# TailBoard.net
KiCad netlist of a schematic drawn in Altium Designer
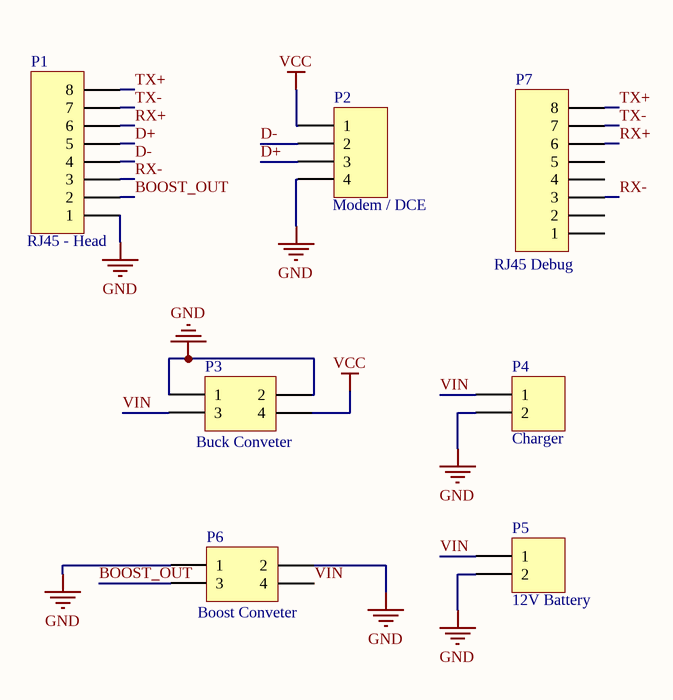
[diagram p0: TailBoard.SchDoc]

(export (version "E")
  (design (tool "Eeschema 10.0.6"))
  (components
    (comp (ref "P1")
      (value "RJ45 - Head")
      (footprint "RJ45")
      (description "Header, 8-Pin")
      (fields (field (name "PUBLISHER") "Altium Limited"))
      (libsource (lib "Miscellaneous Connectors") (part "Header 8"))
    )
    (comp (ref "P2")
      (value "Modem / DCE")
      (footprint "USB_Female")
      (description "Header, 4-Pin")
      (fields (field (name "PUBLISHER") "Altium Limited"))
      (libsource (lib "Miscellaneous Connectors") (part "Header 4"))
    )
    (comp (ref "P3")
      (value "Buck Conveter")
      (footprint "PWR_HEADER")
      (description "Header, 2-Pin, Dual row")
      (fields (field (name "PUBLISHER") "Altium Limited"))
      (libsource (lib "Miscellaneous Connectors") (part "Header 2X2"))
    )
    (comp (ref "P4")
      (value "Charger")
      (footprint "PWR_HEADER - duplicate")
      (description "Header, 2-Pin")
      (fields (field (name "PUBLISHER") "Altium Limited"))
      (libsource (lib "Miscellaneous Connectors") (part "Header 2"))
    )
    (comp (ref "P5")
      (value "12V Battery")
      (footprint "PWR_HEADER - duplicate")
      (description "Header, 2-Pin")
      (fields (field (name "PUBLISHER") "Altium Limited"))
      (libsource (lib "Miscellaneous Connectors") (part "Header 2"))
    )
    (comp (ref "P6")
      (value "Boost Conveter")
      (footprint "PWR_HEADER")
      (description "Header, 2-Pin, Dual row")
      (fields (field (name "PUBLISHER") "Altium Limited"))
      (libsource (lib "Miscellaneous Connectors") (part "Header 2X2"))
    )
    (comp (ref "P7")
      (value "RJ45 Debug")
      (footprint "RJ45")
      (description "Header, 8-Pin")
      (fields (field (name "PUBLISHER") "Altium Limited"))
      (libsource (lib "Miscellaneous Connectors") (part "Header 8"))
    )
  )
  (nets
    (net (code "1") (name "/BOOST_OUT") (class "Default")
      (node (ref "P1") (pin "2") (pinfunction "2_2") (pintype "passive"))
      (node (ref "P6") (pin "3") (pinfunction "3_3") (pintype "passive"))
    )
    (net (code "2") (name "/D+") (class "Default")
      (node (ref "P1") (pin "5") (pinfunction "5_5") (pintype "passive"))
      (node (ref "P2") (pin "3") (pinfunction "3_3") (pintype "passive"))
    )
    (net (code "3") (name "/D-") (class "Default")
      (node (ref "P1") (pin "4") (pinfunction "4_4") (pintype "passive"))
      (node (ref "P2") (pin "2") (pinfunction "2_2") (pintype "passive"))
    )
    (net (code "4") (name "/RX+") (class "Default")
      (node (ref "P1") (pin "6") (pinfunction "6_6") (pintype "passive"))
      (node (ref "P7") (pin "6") (pinfunction "6_6") (pintype "passive"))
    )
    (net (code "5") (name "/RX-") (class "Default")
      (node (ref "P1") (pin "3") (pinfunction "3_3") (pintype "passive"))
      (node (ref "P7") (pin "3") (pinfunction "3_3") (pintype "passive"))
    )
    (net (code "6") (name "/TX+") (class "Default")
      (node (ref "P1") (pin "8") (pinfunction "8_8") (pintype "passive"))
      (node (ref "P7") (pin "8") (pinfunction "8_8") (pintype "passive"))
    )
    (net (code "7") (name "/TX-") (class "Default")
      (node (ref "P1") (pin "7") (pinfunction "7_7") (pintype "passive"))
      (node (ref "P7") (pin "7") (pinfunction "7_7") (pintype "passive"))
    )
    (net (code "8") (name "/VIN") (class "Default")
      (node (ref "P3") (pin "3") (pinfunction "3_3") (pintype "passive"))
      (node (ref "P4") (pin "1") (pinfunction "1_1") (pintype "passive"))
      (node (ref "P5") (pin "1") (pinfunction "1_1") (pintype "passive"))
      (node (ref "P6") (pin "4") (pinfunction "4_4") (pintype "passive"))
    )
    (net (code "9") (name "GND") (class "Default")
      (node (ref "P1") (pin "1") (pinfunction "1_1") (pintype "passive"))
      (node (ref "P2") (pin "4") (pinfunction "4_4") (pintype "passive"))
      (node (ref "P3") (pin "1") (pinfunction "1_1") (pintype "passive"))
      (node (ref "P3") (pin "2") (pinfunction "2_2") (pintype "passive"))
      (node (ref "P4") (pin "2") (pinfunction "2_2") (pintype "passive"))
      (node (ref "P5") (pin "2") (pinfunction "2_2") (pintype "passive"))
      (node (ref "P6") (pin "1") (pinfunction "1_1") (pintype "passive"))
      (node (ref "P6") (pin "2") (pinfunction "2_2") (pintype "passive"))
    )
    (net (code "10") (name "VCC") (class "Default")
      (node (ref "P2") (pin "1") (pinfunction "1_1") (pintype "passive"))
      (node (ref "P3") (pin "4") (pinfunction "4_4") (pintype "passive"))
    )
    (net (code "11") (name "unconnected-(P7-Pad1)") (class "Default")
      (node (ref "P7") (pin "1") (pinfunction "1_1") (pintype "passive"))
    )
    (net (code "12") (name "unconnected-(P7-Pad2)") (class "Default")
      (node (ref "P7") (pin "2") (pinfunction "2_2") (pintype "passive"))
    )
    (net (code "13") (name "unconnected-(P7-Pad4)") (class "Default")
      (node (ref "P7") (pin "4") (pinfunction "4_4") (pintype "passive"))
    )
    (net (code "14") (name "unconnected-(P7-Pad5)") (class "Default")
      (node (ref "P7") (pin "5") (pinfunction "5_5") (pintype "passive"))
    )
  )
)
